# BLDC_Motor_Reverser.net
KiCad netlist of a schematic drawn in Altium Designer
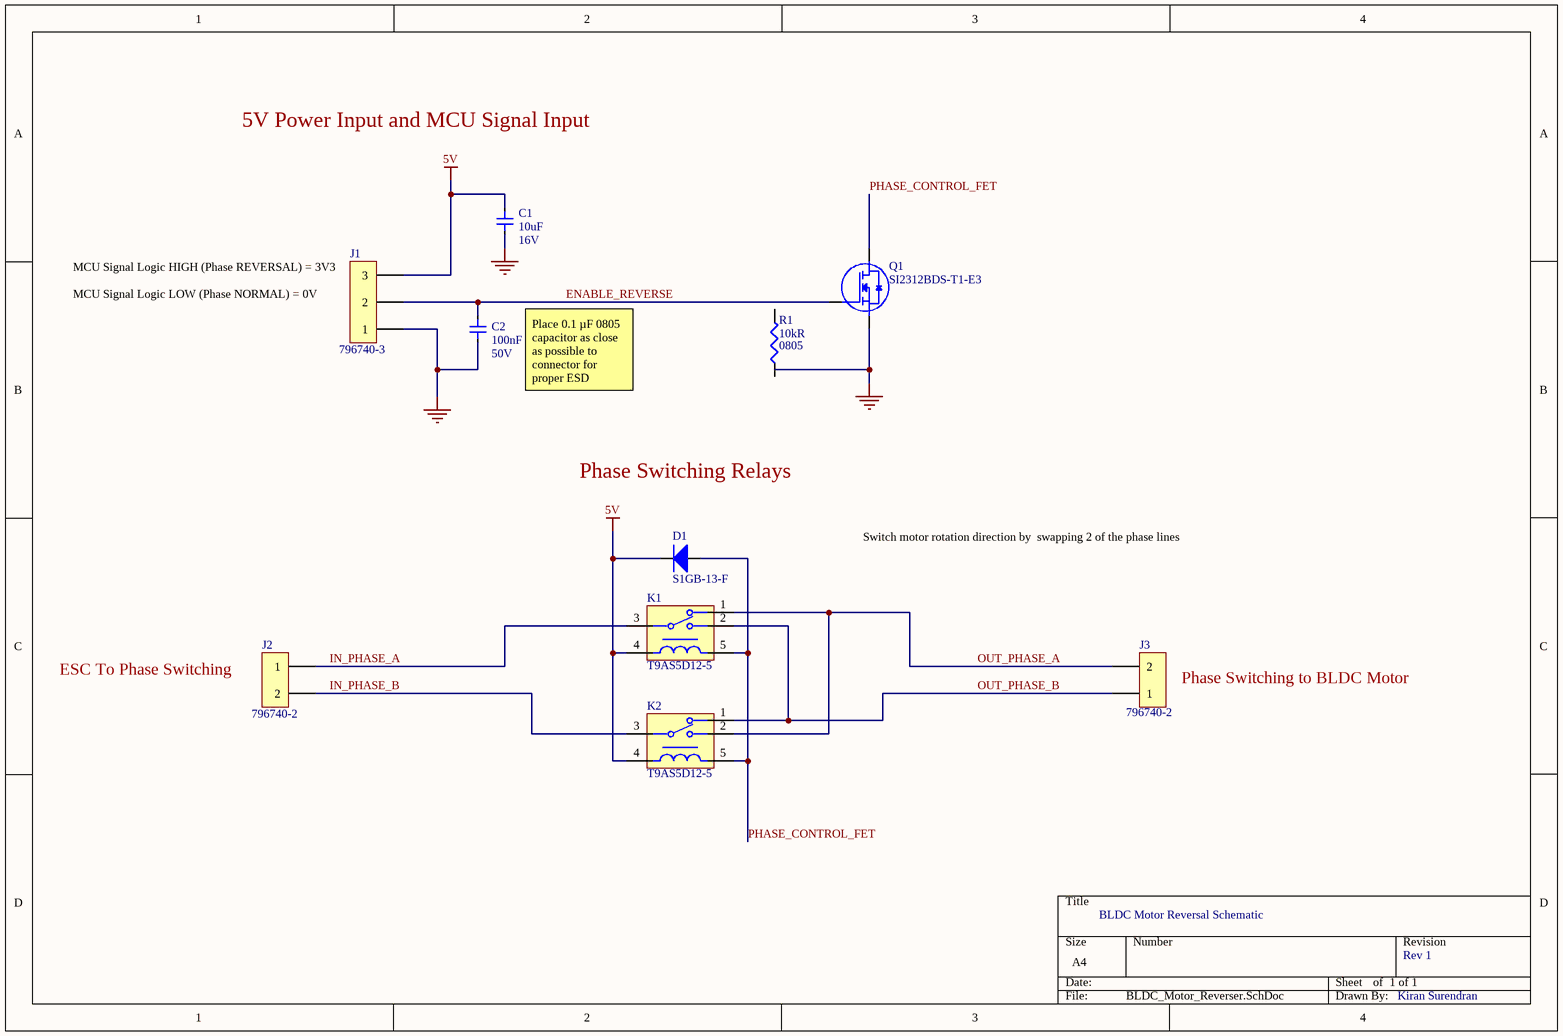
[diagram p0: BLDC_Motor_Reverser.SchDoc]

(export (version "E")
  (design (tool "Eeschema 10.0.6"))
  (components
    (comp (ref "C1")
      (value "C0805C106K4PACTU")
      (footprint "C0805C106K4PACTU")
      (description "CERAMIC CAPACITOR, 10UF, 16V, X5R, 10%, 0805")
      (fields (field (name "VOLTAGE RATING") "16V") (field (name "CAPACITANCE") "10uF"))
      (libsource (lib "BLDC_Motor_Lib") (part "C0805C106K4PACTU"))
    )
    (comp (ref "C2")
      (value "C0805C104K5RACTU")
      (footprint "C0805C104K5RACTU")
      (description "Cap Ceramic 0.1uF 50V X7R 10% SMD 2.0 x 1.2 mm 125 C Paper T/R")
      (fields (field (name "VOLTAGE RATING") "50V") (field (name "CAPACITANCE") "100nF"))
      (libsource (lib "BLDC_Motor_Lib") (part "C0805C104K5RACTU"))
    )
    (comp (ref "D1")
      (value "S1GB-13-F")
      (footprint "S1GB-13-F")
      (description "Flyback Diode for SPDT")
      (libsource (lib "BLDC_Motor_Lib") (part "S1GB-13-F"))
    )
    (comp (ref "J1")
      (value "796740-3")
      (footprint "796740-3")
      (description "TERM BLK 3P SIDE ENT 6.35MM PCB")
      (libsource (lib "BLDC_Motor_Lib") (part "796740-3"))
    )
    (comp (ref "J2")
      (value "796740-2")
      (footprint "796740-2")
      (description "TERMINAL BLOCK, PLUG, 2POS, 24-10AWG")
      (fields (field (name "MANUFACTURER") "TE Connectivity"))
      (libsource (lib "") (part "796740-2_1"))
    )
    (comp (ref "J3")
      (value "796740-2")
      (footprint "796740-2")
      (description "TERMINAL BLOCK, PLUG, 2POS, 24-10AWG")
      (fields (field (name "MANUFACTURER") "TE Connectivity"))
      (libsource (lib "BLDC_Motor_Lib") (part "796740-2"))
    )
    (comp (ref "K1")
      (value "T9AS5D12-5")
      (footprint "T9AS5D12-5")
      (description "RELAY GEN PURPOSE SPDT 20A 5V")
      (libsource (lib "BLDC_Motor_Lib") (part "T9AS5D12-5"))
    )
    (comp (ref "K2")
      (value "T9AS5D12-5")
      (footprint "T9AS5D12-5")
      (description "RELAY GEN PURPOSE SPDT 20A 5V")
      (libsource (lib "BLDC_Motor_Lib") (part "T9AS5D12-5"))
    )
    (comp (ref "Q1")
      (value "SI2312BDS-T1-E3")
      (footprint "SI2312BDS-T1-E3")
      (description "MOSFET")
      (libsource (lib "BLDC_Motor_Lib") (part "SI2312BDS-T1-E3"))
    )
    (comp (ref "R1")
      (value "RC0805JR-0710KL")
      (footprint "RC0805JR-0710KL")
      (description "Res Thick Film 0805 10K Ohm 5% 1/8W ±100ppm/°C Molded SMD Paper T/R")
      (fields
        (field (name "TOLERANCE") "5%")
        (field (name "PACKAGE") "0805")
        (field (name "RESISTANCE") "10kR")
      )
      (libsource (lib "BLDC_Motor_Lib") (part "RC0805JR-0710KL"))
    )
  )
  (nets
    (net (code "1") (name "/ENABLE_REVERSE") (class "Default")
      (node (ref "C2") (pin "2") (pintype "passive"))
      (node (ref "J1") (pin "2") (pinfunction "2_2") (pintype "passive"))
      (node (ref "Q1") (pin "1") (pinfunction "Gate_1") (pintype "passive"))
    )
    (net (code "2") (name "/IN_PHASE_A") (class "Default")
      (node (ref "J2") (pin "1") (pinfunction "1_1") (pintype "passive"))
      (node (ref "K1") (pin "3") (pinfunction "COM_3") (pintype "passive"))
    )
    (net (code "3") (name "/IN_PHASE_B") (class "Default")
      (node (ref "J2") (pin "2") (pinfunction "2_2") (pintype "passive"))
      (node (ref "K2") (pin "3") (pinfunction "COM_3") (pintype "passive"))
    )
    (net (code "4") (name "/OUT_PHASE_A") (class "Default")
      (node (ref "J3") (pin "2") (pinfunction "2_2") (pintype "passive"))
      (node (ref "K1") (pin "1") (pinfunction "NC_1") (pintype "passive"))
      (node (ref "K2") (pin "2") (pinfunction "NO_2") (pintype "passive"))
    )
    (net (code "5") (name "/OUT_PHASE_B") (class "Default")
      (node (ref "J3") (pin "1") (pinfunction "1_1") (pintype "passive"))
      (node (ref "K1") (pin "2") (pinfunction "NO_2") (pintype "passive"))
      (node (ref "K2") (pin "1") (pinfunction "NC_1") (pintype "passive"))
    )
    (net (code "6") (name "/PHASE_CONTROL_FET") (class "Default")
      (node (ref "D1") (pin "2") (pinfunction "+_2") (pintype "passive"))
      (node (ref "K1") (pin "5") (pinfunction "5_5") (pintype "passive"))
      (node (ref "K2") (pin "5") (pinfunction "5_5") (pintype "passive"))
      (node (ref "Q1") (pin "3") (pinfunction "Drain_3") (pintype "passive"))
    )
    (net (code "7") (name "5V") (class "Default")
      (node (ref "C1") (pin "2") (pintype "passive"))
      (node (ref "D1") (pin "1") (pinfunction "-_1") (pintype "passive"))
      (node (ref "J1") (pin "3") (pinfunction "3_3") (pintype "passive"))
      (node (ref "K1") (pin "4") (pinfunction "4_4") (pintype "passive"))
      (node (ref "K2") (pin "4") (pinfunction "4_4") (pintype "passive"))
    )
    (net (code "8") (name "GND") (class "Default")
      (node (ref "C1") (pin "1") (pintype "passive"))
      (node (ref "C2") (pin "1") (pintype "passive"))
      (node (ref "J1") (pin "1") (pinfunction "1_1") (pintype "passive"))
      (node (ref "Q1") (pin "2") (pinfunction "Source_2") (pintype "passive"))
    )
    (net (code "9") (name "unconnected-(R1-Pad1)") (class "Default")
      (node (ref "R1") (pin "1") (pintype "passive"))
    )
    (net (code "10") (name "unconnected-(R1-Pad2)") (class "Default")
      (node (ref "R1") (pin "2") (pintype "passive"))
    )
  )
)
